# SL_FPGA_Auto_2E.net
KiCad netlist of a schematic drawn in Altium Designer
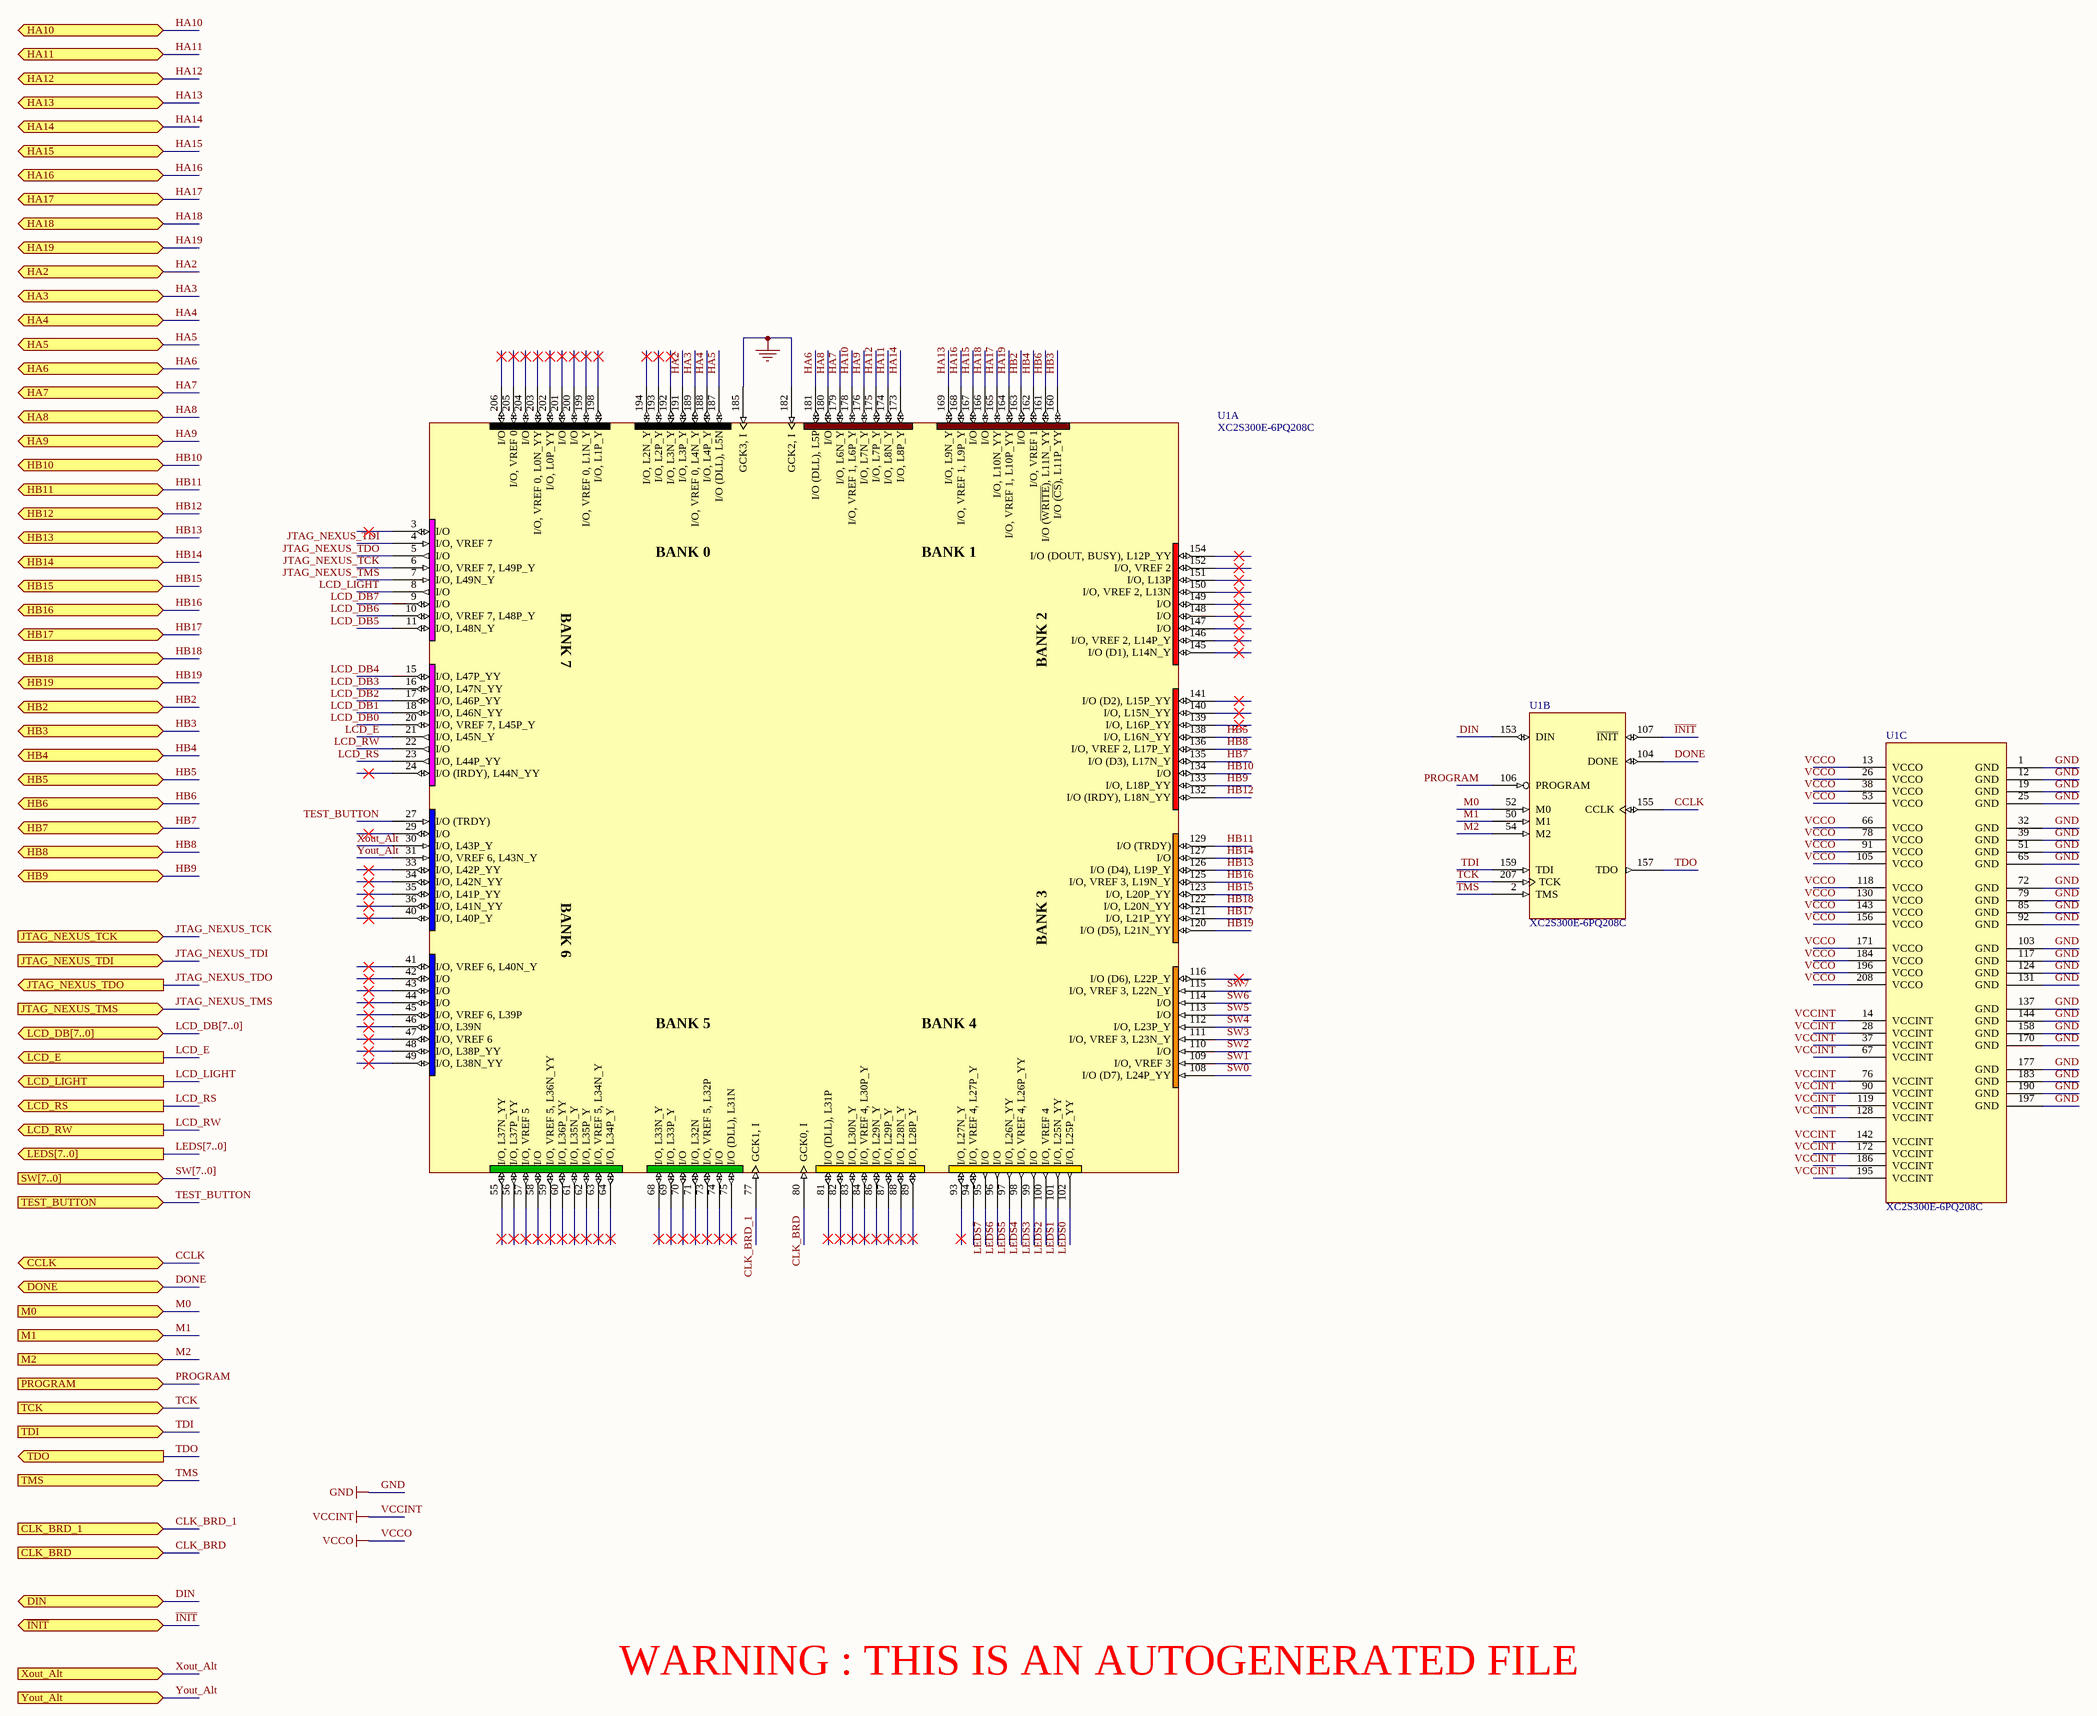
[diagram p0: SL_FPGA_Auto_2E.SchDoc]

(export (version "E")
  (design (tool "Eeschema 10.0.6"))
  (components
    (comp (ref "U1")
      (value "XC2S300E-6PQ208C")
      (footprint "Spirit_Level_Project:PQ208")
      (description "Spartan-IIE 1.8V FPGA, 208-Pin PQFP, Standard Performance, Commercial Grade")
      (fields (field (name "PUBLISHER") "Altium Limited"))
      (libsource (lib "SpiritLevel_2E") (part "XC2S300E-6PQ208C"))
    )
  )
  (nets
    (net (code "1") (name "/CCLK") (class "Default")
      (node (ref "U1") (pin "155") (pinfunction "CCLK_155") (pintype "bidirectional"))
    )
    (net (code "2") (name "/CLK_BRD") (class "Default")
      (node (ref "U1") (pin "80") (pinfunction "GCK0,_I_80") (pintype "input"))
    )
    (net (code "3") (name "/CLK_BRD_1") (class "Default")
      (node (ref "U1") (pin "77") (pinfunction "GCK1,_I_77") (pintype "input"))
    )
    (net (code "4") (name "/DIN") (class "Default")
      (node (ref "U1") (pin "153") (pinfunction "DIN_153") (pintype "bidirectional"))
    )
    (net (code "5") (name "/DONE") (class "Default")
      (node (ref "U1") (pin "104") (pinfunction "DONE_104") (pintype "bidirectional"))
    )
    (net (code "6") (name "/HA2") (class "Default")
      (node (ref "U1") (pin "191") (pinfunction "I/O,_L3P_Y_191") (pintype "bidirectional"))
    )
    (net (code "7") (name "/HA3") (class "Default")
      (node (ref "U1") (pin "189") (pinfunction "I/O,_VREF_0,_L4N_Y_189") (pintype "bidirectional"))
    )
    (net (code "8") (name "/HA4") (class "Default")
      (node (ref "U1") (pin "188") (pinfunction "I/O,_L4P_Y_188") (pintype "bidirectional"))
    )
    (net (code "9") (name "/HA5") (class "Default")
      (node (ref "U1") (pin "187") (pinfunction "I/O_(DLL),_L5N_187") (pintype "bidirectional"))
    )
    (net (code "10") (name "/HA6") (class "Default")
      (node (ref "U1") (pin "181") (pinfunction "I/O_(DLL),_L5P_181") (pintype "bidirectional"))
    )
    (net (code "11") (name "/HA7") (class "Default")
      (node (ref "U1") (pin "179") (pinfunction "I/O,_L6N_Y_179") (pintype "bidirectional"))
    )
    (net (code "12") (name "/HA8") (class "Default")
      (node (ref "U1") (pin "180") (pinfunction "I/O_180") (pintype "bidirectional"))
    )
    (net (code "13") (name "/HA9") (class "Default")
      (node (ref "U1") (pin "176") (pinfunction "I/O,_L7N_Y_176") (pintype "bidirectional"))
    )
    (net (code "14") (name "/HA10") (class "Default")
      (node (ref "U1") (pin "178") (pinfunction "I/O,_VREF_1,_L6P_Y_178") (pintype "bidirectional"))
    )
    (net (code "15") (name "/HA11") (class "Default")
      (node (ref "U1") (pin "174") (pinfunction "I/O,_L8N_Y_174") (pintype "bidirectional"))
    )
    (net (code "16") (name "/HA12") (class "Default")
      (node (ref "U1") (pin "175") (pinfunction "I/O,_L7P_Y_175") (pintype "bidirectional"))
    )
    (net (code "17") (name "/HA13") (class "Default")
      (node (ref "U1") (pin "169") (pinfunction "I/O,_L9N_Y_169") (pintype "bidirectional"))
    )
    (net (code "18") (name "/HA14") (class "Default")
      (node (ref "U1") (pin "173") (pinfunction "I/O,_L8P_Y_173") (pintype "bidirectional"))
    )
    (net (code "19") (name "/HA15") (class "Default")
      (node (ref "U1") (pin "167") (pinfunction "I/O_167") (pintype "bidirectional"))
    )
    (net (code "20") (name "/HA16") (class "Default")
      (node (ref "U1") (pin "168") (pinfunction "I/O,_VREF_1,_L9P_Y_168") (pintype "bidirectional"))
    )
    (net (code "21") (name "/HA17") (class "Default")
      (node (ref "U1") (pin "165") (pinfunction "I/O,_L10N_YY_165") (pintype "bidirectional"))
    )
    (net (code "22") (name "/HA18") (class "Default")
      (node (ref "U1") (pin "166") (pinfunction "I/O_166") (pintype "bidirectional"))
    )
    (net (code "23") (name "/HA19") (class "Default")
      (node (ref "U1") (pin "164") (pinfunction "I/O,_VREF_1,_L10P_YY_164") (pintype "bidirectional"))
    )
    (net (code "24") (name "/HB2") (class "Default")
      (node (ref "U1") (pin "163") (pinfunction "I/O_163") (pintype "bidirectional"))
    )
    (net (code "25") (name "/HB3") (class "Default")
      (node (ref "U1") (pin "160") (pinfunction "I/O_(~{CS}),_L11P_YY_160") (pintype "bidirectional"))
    )
    (net (code "26") (name "/HB4") (class "Default")
      (node (ref "U1") (pin "162") (pinfunction "I/O,_VREF_1_162") (pintype "bidirectional"))
    )
    (net (code "27") (name "/HB5") (class "Default")
      (node (ref "U1") (pin "138") (pinfunction "I/O,_L16N_YY_138") (pintype "bidirectional"))
    )
    (net (code "28") (name "/HB6") (class "Default")
      (node (ref "U1") (pin "161") (pinfunction "I/O_(~{WRITE}),_L11N_YY_161") (pintype "bidirectional"))
    )
    (net (code "29") (name "/HB7") (class "Default")
      (node (ref "U1") (pin "135") (pinfunction "I/O_(D3),_L17N_Y_135") (pintype "bidirectional"))
    )
    (net (code "30") (name "/HB8") (class "Default")
      (node (ref "U1") (pin "136") (pinfunction "I/O,_VREF_2,_L17P_Y_136") (pintype "bidirectional"))
    )
    (net (code "31") (name "/HB9") (class "Default")
      (node (ref "U1") (pin "133") (pinfunction "I/O,_L18P_YY_133") (pintype "bidirectional"))
    )
    (net (code "32") (name "/HB10") (class "Default")
      (node (ref "U1") (pin "134") (pinfunction "I/O_134") (pintype "bidirectional"))
    )
    (net (code "33") (name "/HB11") (class "Default")
      (node (ref "U1") (pin "129") (pinfunction "I/O_(TRDY)_129") (pintype "bidirectional"))
    )
    (net (code "34") (name "/HB12") (class "Default")
      (node (ref "U1") (pin "132") (pinfunction "I/O_(IRDY),_L18N_YY_132") (pintype "bidirectional"))
    )
    (net (code "35") (name "/HB13") (class "Default")
      (node (ref "U1") (pin "126") (pinfunction "I/O_(D4),_L19P_Y_126") (pintype "bidirectional"))
    )
    (net (code "36") (name "/HB14") (class "Default")
      (node (ref "U1") (pin "127") (pinfunction "I/O_127") (pintype "bidirectional"))
    )
    (net (code "37") (name "/HB15") (class "Default")
      (node (ref "U1") (pin "123") (pinfunction "I/O,_L20P_YY_123") (pintype "bidirectional"))
    )
    (net (code "38") (name "/HB16") (class "Default")
      (node (ref "U1") (pin "125") (pinfunction "I/O,_VREF_3,_L19N_Y_125") (pintype "bidirectional"))
    )
    (net (code "39") (name "/HB17") (class "Default")
      (node (ref "U1") (pin "121") (pinfunction "I/O,_L21P_YY_121") (pintype "bidirectional"))
    )
    (net (code "40") (name "/HB18") (class "Default")
      (node (ref "U1") (pin "122") (pinfunction "I/O,_L20N_YY_122") (pintype "bidirectional"))
    )
    (net (code "41") (name "/HB19") (class "Default")
      (node (ref "U1") (pin "120") (pinfunction "I/O_(D5),_L21N_YY_120") (pintype "bidirectional"))
    )
    (net (code "42") (name "/JTAG_NEXUS_TCK") (class "Default")
      (node (ref "U1") (pin "6") (pinfunction "I/O,_VREF_7,_L49P_Y_6") (pintype "input"))
    )
    (net (code "43") (name "/JTAG_NEXUS_TDI") (class "Default")
      (node (ref "U1") (pin "4") (pinfunction "I/O,_VREF_7_4") (pintype "input"))
    )
    (net (code "44") (name "/JTAG_NEXUS_TDO") (class "Default")
      (node (ref "U1") (pin "5") (pinfunction "I/O_5") (pintype "output"))
    )
    (net (code "45") (name "/JTAG_NEXUS_TMS") (class "Default")
      (node (ref "U1") (pin "7") (pinfunction "I/O,_L49N_Y_7") (pintype "input"))
    )
    (net (code "46") (name "/LCD_DB0") (class "Default")
      (node (ref "U1") (pin "20") (pinfunction "I/O,_VREF_7,_L45P_Y_20") (pintype "bidirectional"))
    )
    (net (code "47") (name "/LCD_DB1") (class "Default")
      (node (ref "U1") (pin "18") (pinfunction "I/O,_L46N_YY_18") (pintype "bidirectional"))
    )
    (net (code "48") (name "/LCD_DB2") (class "Default")
      (node (ref "U1") (pin "17") (pinfunction "I/O,_L46P_YY_17") (pintype "bidirectional"))
    )
    (net (code "49") (name "/LCD_DB3") (class "Default")
      (node (ref "U1") (pin "16") (pinfunction "I/O,_L47N_YY_16") (pintype "bidirectional"))
    )
    (net (code "50") (name "/LCD_DB4") (class "Default")
      (node (ref "U1") (pin "15") (pinfunction "I/O,_L47P_YY_15") (pintype "bidirectional"))
    )
    (net (code "51") (name "/LCD_DB5") (class "Default")
      (node (ref "U1") (pin "11") (pinfunction "I/O,_L48N_Y_11") (pintype "bidirectional"))
    )
    (net (code "52") (name "/LCD_DB6") (class "Default")
      (node (ref "U1") (pin "10") (pinfunction "I/O,_VREF_7,_L48P_Y_10") (pintype "bidirectional"))
    )
    (net (code "53") (name "/LCD_DB7") (class "Default")
      (node (ref "U1") (pin "9") (pinfunction "I/O_9") (pintype "bidirectional"))
    )
    (net (code "55") (name "/LCD_E") (class "Default")
      (node (ref "U1") (pin "21") (pinfunction "I/O,_L45N_Y_21") (pintype "output"))
    )
    (net (code "56") (name "/LCD_LIGHT") (class "Default")
      (node (ref "U1") (pin "8") (pinfunction "I/O_8") (pintype "output"))
    )
    (net (code "57") (name "/LCD_RS") (class "Default")
      (node (ref "U1") (pin "23") (pinfunction "I/O,_L44P_YY_23") (pintype "output"))
    )
    (net (code "58") (name "/LCD_RW") (class "Default")
      (node (ref "U1") (pin "22") (pinfunction "I/O_22") (pintype "output"))
    )
    (net (code "59") (name "/LEDS0") (class "Default")
      (node (ref "U1") (pin "102") (pinfunction "I/O,_L25P_YY_102") (pintype "output"))
    )
    (net (code "60") (name "/LEDS1") (class "Default")
      (node (ref "U1") (pin "101") (pinfunction "I/O,_L25N_YY_101") (pintype "output"))
    )
    (net (code "61") (name "/LEDS2") (class "Default")
      (node (ref "U1") (pin "100") (pinfunction "I/O,_VREF_4_100") (pintype "output"))
    )
    (net (code "62") (name "/LEDS3") (class "Default")
      (node (ref "U1") (pin "99") (pinfunction "I/O_99") (pintype "output"))
    )
    (net (code "63") (name "/LEDS4") (class "Default")
      (node (ref "U1") (pin "98") (pinfunction "I/O,_VREF_4,_L26P_YY_98") (pintype "output"))
    )
    (net (code "64") (name "/LEDS5") (class "Default")
      (node (ref "U1") (pin "97") (pinfunction "I/O,_L26N_YY_97") (pintype "output"))
    )
    (net (code "65") (name "/LEDS6") (class "Default")
      (node (ref "U1") (pin "96") (pinfunction "I/O_96") (pintype "output"))
    )
    (net (code "66") (name "/LEDS7") (class "Default")
      (node (ref "U1") (pin "95") (pinfunction "I/O_95") (pintype "output"))
    )
    (net (code "68") (name "/M0") (class "Default")
      (node (ref "U1") (pin "52") (pinfunction "M0_52") (pintype "input"))
    )
    (net (code "69") (name "/M1") (class "Default")
      (node (ref "U1") (pin "50") (pinfunction "M1_50") (pintype "input"))
    )
    (net (code "70") (name "/M2") (class "Default")
      (node (ref "U1") (pin "54") (pinfunction "M2_54") (pintype "input"))
    )
    (net (code "71") (name "/PROGRAM") (class "Default")
      (node (ref "U1") (pin "106") (pinfunction "PROGRAM_106") (pintype "input"))
    )
    (net (code "72") (name "/SW0") (class "Default")
      (node (ref "U1") (pin "108") (pinfunction "I/O_(D7),_L24P_YY_108") (pintype "input"))
    )
    (net (code "73") (name "/SW1") (class "Default")
      (node (ref "U1") (pin "109") (pinfunction "I/O,_VREF_3_109") (pintype "input"))
    )
    (net (code "74") (name "/SW2") (class "Default")
      (node (ref "U1") (pin "110") (pinfunction "I/O_110") (pintype "input"))
    )
    (net (code "75") (name "/SW3") (class "Default")
      (node (ref "U1") (pin "111") (pinfunction "I/O,_VREF_3,_L23N_Y_111") (pintype "input"))
    )
    (net (code "76") (name "/SW4") (class "Default")
      (node (ref "U1") (pin "112") (pinfunction "I/O,_L23P_Y_112") (pintype "input"))
    )
    (net (code "77") (name "/SW5") (class "Default")
      (node (ref "U1") (pin "113") (pinfunction "I/O_113") (pintype "input"))
    )
    (net (code "78") (name "/SW6") (class "Default")
      (node (ref "U1") (pin "114") (pinfunction "I/O_114") (pintype "input"))
    )
    (net (code "79") (name "/SW7") (class "Default")
      (node (ref "U1") (pin "115") (pinfunction "I/O,_VREF_3,_L22N_Y_115") (pintype "input"))
    )
    (net (code "81") (name "/TCK") (class "Default")
      (node (ref "U1") (pin "207") (pinfunction "TCK_207") (pintype "input"))
    )
    (net (code "82") (name "/TDI") (class "Default")
      (node (ref "U1") (pin "159") (pinfunction "TDI_159") (pintype "input"))
    )
    (net (code "83") (name "/TDO") (class "Default")
      (node (ref "U1") (pin "157") (pinfunction "TDO_157") (pintype "output"))
    )
    (net (code "84") (name "/TEST_BUTTON") (class "Default")
      (node (ref "U1") (pin "27") (pinfunction "I/O_(TRDY)_27") (pintype "input"))
    )
    (net (code "85") (name "/TMS") (class "Default")
      (node (ref "U1") (pin "2") (pinfunction "TMS_2") (pintype "input"))
    )
    (net (code "86") (name "/Xout_Alt") (class "Default")
      (node (ref "U1") (pin "30") (pinfunction "I/O,_L43P_Y_30") (pintype "input"))
    )
    (net (code "87") (name "/Yout_Alt") (class "Default")
      (node (ref "U1") (pin "31") (pinfunction "I/O,_VREF_6,_L43N_Y_31") (pintype "input"))
    )
    (net (code "88") (name "/~{INIT}") (class "Default")
      (node (ref "U1") (pin "107") (pinfunction "~{INIT}_107") (pintype "bidirectional"))
    )
    (net (code "89") (name "GND") (class "Default")
      (node (ref "U1") (pin "1") (pinfunction "GND_1") (pintype "power_in"))
      (node (ref "U1") (pin "103") (pinfunction "GND_103") (pintype "power_in"))
      (node (ref "U1") (pin "117") (pinfunction "GND_117") (pintype "power_in"))
      (node (ref "U1") (pin "12") (pinfunction "GND_12") (pintype "power_in"))
      (node (ref "U1") (pin "124") (pinfunction "GND_124") (pintype "power_in"))
      (node (ref "U1") (pin "131") (pinfunction "GND_131") (pintype "power_in"))
      (node (ref "U1") (pin "137") (pinfunction "GND_137") (pintype "power_in"))
      (node (ref "U1") (pin "144") (pinfunction "GND_144") (pintype "power_in"))
      (node (ref "U1") (pin "158") (pinfunction "GND_158") (pintype "power_in"))
      (node (ref "U1") (pin "170") (pinfunction "GND_170") (pintype "power_in"))
      (node (ref "U1") (pin "177") (pinfunction "GND_177") (pintype "power_in"))
      (node (ref "U1") (pin "182") (pinfunction "GCK2,_I_182") (pintype "input"))
      (node (ref "U1") (pin "183") (pinfunction "GND_183") (pintype "power_in"))
      (node (ref "U1") (pin "185") (pinfunction "GCK3,_I_185") (pintype "input"))
      (node (ref "U1") (pin "19") (pinfunction "GND_19") (pintype "power_in"))
      (node (ref "U1") (pin "190") (pinfunction "GND_190") (pintype "power_in"))
      (node (ref "U1") (pin "197") (pinfunction "GND_197") (pintype "power_in"))
      (node (ref "U1") (pin "25") (pinfunction "GND_25") (pintype "power_in"))
      (node (ref "U1") (pin "32") (pinfunction "GND_32") (pintype "power_in"))
      (node (ref "U1") (pin "39") (pinfunction "GND_39") (pintype "power_in"))
      (node (ref "U1") (pin "51") (pinfunction "GND_51") (pintype "power_in"))
      (node (ref "U1") (pin "65") (pinfunction "GND_65") (pintype "power_in"))
      (node (ref "U1") (pin "72") (pinfunction "GND_72") (pintype "power_in"))
      (node (ref "U1") (pin "79") (pinfunction "GND_79") (pintype "power_in"))
      (node (ref "U1") (pin "85") (pinfunction "GND_85") (pintype "power_in"))
      (node (ref "U1") (pin "92") (pinfunction "GND_92") (pintype "power_in"))
    )
    (net (code "90") (name "VCCINT") (class "Default")
      (node (ref "U1") (pin "119") (pinfunction "VCCINT_119") (pintype "power_in"))
      (node (ref "U1") (pin "128") (pinfunction "VCCINT_128") (pintype "power_in"))
      (node (ref "U1") (pin "14") (pinfunction "VCCINT_14") (pintype "power_in"))
      (node (ref "U1") (pin "142") (pinfunction "VCCINT_142") (pintype "power_in"))
      (node (ref "U1") (pin "172") (pinfunction "VCCINT_172") (pintype "power_in"))
      (node (ref "U1") (pin "186") (pinfunction "VCCINT_186") (pintype "power_in"))
      (node (ref "U1") (pin "195") (pinfunction "VCCINT_195") (pintype "power_in"))
      (node (ref "U1") (pin "28") (pinfunction "VCCINT_28") (pintype "power_in"))
      (node (ref "U1") (pin "37") (pinfunction "VCCINT_37") (pintype "power_in"))
      (node (ref "U1") (pin "67") (pinfunction "VCCINT_67") (pintype "power_in"))
      (node (ref "U1") (pin "76") (pinfunction "VCCINT_76") (pintype "power_in"))
      (node (ref "U1") (pin "90") (pinfunction "VCCINT_90") (pintype "power_in"))
    )
    (net (code "91") (name "VCCO") (class "Default")
      (node (ref "U1") (pin "105") (pinfunction "VCCO_105") (pintype "power_in"))
      (node (ref "U1") (pin "118") (pinfunction "VCCO_118") (pintype "power_in"))
      (node (ref "U1") (pin "13") (pinfunction "VCCO_13") (pintype "power_in"))
      (node (ref "U1") (pin "130") (pinfunction "VCCO_130") (pintype "power_in"))
      (node (ref "U1") (pin "143") (pinfunction "VCCO_143") (pintype "power_in"))
      (node (ref "U1") (pin "156") (pinfunction "VCCO_156") (pintype "power_in"))
      (node (ref "U1") (pin "171") (pinfunction "VCCO_171") (pintype "power_in"))
      (node (ref "U1") (pin "184") (pinfunction "VCCO_184") (pintype "power_in"))
      (node (ref "U1") (pin "196") (pinfunction "VCCO_196") (pintype "power_in"))
      (node (ref "U1") (pin "208") (pinfunction "VCCO_208") (pintype "power_in"))
      (node (ref "U1") (pin "26") (pinfunction "VCCO_26") (pintype "power_in"))
      (node (ref "U1") (pin "38") (pinfunction "VCCO_38") (pintype "power_in"))
      (node (ref "U1") (pin "53") (pinfunction "VCCO_53") (pintype "power_in"))
      (node (ref "U1") (pin "66") (pinfunction "VCCO_66") (pintype "power_in"))
      (node (ref "U1") (pin "78") (pinfunction "VCCO_78") (pintype "power_in"))
      (node (ref "U1") (pin "91") (pinfunction "VCCO_91") (pintype "power_in"))
    )
    (net (code "92") (name "unconnected-(U1A-I{slash}O,_L0P_YY-Pad202)") (class "Default")
      (node (ref "U1") (pin "202") (pinfunction "I/O,_L0P_YY_202") (pintype "bidirectional"))
    )
    (net (code "93") (name "unconnected-(U1A-I{slash}O,_L1P_Y-Pad198)") (class "Default")
      (node (ref "U1") (pin "198") (pinfunction "I/O,_L1P_Y_198") (pintype "bidirectional"))
    )
    (net (code "94") (name "unconnected-(U1A-I{slash}O,_L2N_Y-Pad194)") (class "Default")
      (node (ref "U1") (pin "194") (pinfunction "I/O,_L2N_Y_194") (pintype "bidirectional"))
    )
    (net (code "95") (name "unconnected-(U1A-I{slash}O,_L2P_Y-Pad193)") (class "Default")
      (node (ref "U1") (pin "193") (pinfunction "I/O,_L2P_Y_193") (pintype "bidirectional"))
    )
    (net (code "96") (name "unconnected-(U1A-I{slash}O,_L3N_Y-Pad192)") (class "Default")
      (node (ref "U1") (pin "192") (pinfunction "I/O,_L3N_Y_192") (pintype "bidirectional"))
    )
    (net (code "97") (name "unconnected-(U1A-I{slash}O,_L13P-Pad151)") (class "Default")
      (node (ref "U1") (pin "151") (pinfunction "I/O,_L13P_151") (pintype "bidirectional"))
    )
    (net (code "98") (name "unconnected-(U1A-I{slash}O,_L15N_YY-Pad140)") (class "Default")
      (node (ref "U1") (pin "140") (pinfunction "I/O,_L15N_YY_140") (pintype "bidirectional"))
    )
    (net (code "99") (name "unconnected-(U1A-I{slash}O,_L16P_YY-Pad139)") (class "Default")
      (node (ref "U1") (pin "139") (pinfunction "I/O,_L16P_YY_139") (pintype "bidirectional"))
    )
    (net (code "100") (name "unconnected-(U1A-I{slash}O,_L27N_Y-Pad93)") (class "Default")
      (node (ref "U1") (pin "93") (pinfunction "I/O,_L27N_Y_93") (pintype "bidirectional"))
    )
    (net (code "101") (name "unconnected-(U1A-I{slash}O,_L28N_Y-Pad88)") (class "Default")
      (node (ref "U1") (pin "88") (pinfunction "I/O,_L28N_Y_88") (pintype "bidirectional"))
    )
    (net (code "102") (name "unconnected-(U1A-I{slash}O,_L28P_Y-Pad89)") (class "Default")
      (node (ref "U1") (pin "89") (pinfunction "I/O,_L28P_Y_89") (pintype "bidirectional"))
    )
    (net (code "103") (name "unconnected-(U1A-I{slash}O,_L29N_Y-Pad86)") (class "Default")
      (node (ref "U1") (pin "86") (pinfunction "I/O,_L29N_Y_86") (pintype "bidirectional"))
    )
    (net (code "104") (name "unconnected-(U1A-I{slash}O,_L29P_Y-Pad87)") (class "Default")
      (node (ref "U1") (pin "87") (pinfunction "I/O,_L29P_Y_87") (pintype "bidirectional"))
    )
    (net (code "105") (name "unconnected-(U1A-I{slash}O,_L30N_Y-Pad83)") (class "Default")
      (node (ref "U1") (pin "83") (pinfunction "I/O,_L30N_Y_83") (pintype "bidirectional"))
    )
    (net (code "106") (name "unconnected-(U1A-I{slash}O,_L32N-Pad71)") (class "Default")
      (node (ref "U1") (pin "71") (pinfunction "I/O,_L32N_71") (pintype "bidirectional"))
    )
    (net (code "107") (name "unconnected-(U1A-I{slash}O,_L33N_Y-Pad68)") (class "Default")
      (node (ref "U1") (pin "68") (pinfunction "I/O,_L33N_Y_68") (pintype "bidirectional"))
    )
    (net (code "108") (name "unconnected-(U1A-I{slash}O,_L33P_Y-Pad69)") (class "Default")
      (node (ref "U1") (pin "69") (pinfunction "I/O,_L33P_Y_69") (pintype "bidirectional"))
    )
    (net (code "109") (name "unconnected-(U1A-I{slash}O,_L34P_Y-Pad64)") (class "Default")
      (node (ref "U1") (pin "64") (pinfunction "I/O,_L34P_Y_64") (pintype "bidirectional"))
    )
    (net (code "110") (name "unconnected-(U1A-I{slash}O,_L35N_Y-Pad61)") (class "Default")
      (node (ref "U1") (pin "61") (pinfunction "I/O,_L35N_Y_61") (pintype "bidirectional"))
    )
    (net (code "111") (name "unconnected-(U1A-I{slash}O,_L35P_Y-Pad62)") (class "Default")
      (node (ref "U1") (pin "62") (pinfunction "I/O,_L35P_Y_62") (pintype "bidirectional"))
    )
    (net (code "112") (name "unconnected-(U1A-I{slash}O,_L36P_YY-Pad60)") (class "Default")
      (node (ref "U1") (pin "60") (pinfunction "I/O,_L36P_YY_60") (pintype "bidirectional"))
    )
    (net (code "113") (name "unconnected-(U1A-I{slash}O,_L37N_YY-Pad55)") (class "Default")
      (node (ref "U1") (pin "55") (pinfunction "I/O,_L37N_YY_55") (pintype "bidirectional"))
    )
    (net (code "114") (name "unconnected-(U1A-I{slash}O,_L37P_YY-Pad56)") (class "Default")
      (node (ref "U1") (pin "56") (pinfunction "I/O,_L37P_YY_56") (pintype "bidirectional"))
    )
    (net (code "115") (name "unconnected-(U1A-I{slash}O,_L38N_YY-Pad49)") (class "Default")
      (node (ref "U1") (pin "49") (pinfunction "I/O,_L38N_YY_49") (pintype "bidirectional"))
    )
    (net (code "116") (name "unconnected-(U1A-I{slash}O,_L38P_YY-Pad48)") (class "Default")
      (node (ref "U1") (pin "48") (pinfunction "I/O,_L38P_YY_48") (pintype "bidirectional"))
    )
    (net (code "117") (name "unconnected-(U1A-I{slash}O,_L39N-Pad46)") (class "Default")
      (node (ref "U1") (pin "46") (pinfunction "I/O,_L39N_46") (pintype "bidirectional"))
    )
    (net (code "118") (name "unconnected-(U1A-I{slash}O,_L40P_Y-Pad40)") (class "Default")
      (node (ref "U1") (pin "40") (pinfunction "I/O,_L40P_Y_40") (pintype "bidirectional"))
    )
    (net (code "119") (name "unconnected-(U1A-I{slash}O,_L41N_YY-Pad36)") (class "Default")
      (node (ref "U1") (pin "36") (pinfunction "I/O,_L41N_YY_36") (pintype "bidirectional"))
    )
    (net (code "120") (name "unconnected-(U1A-I{slash}O,_L41P_YY-Pad35)") (class "Default")
      (node (ref "U1") (pin "35") (pinfunction "I/O,_L41P_YY_35") (pintype "bidirectional"))
    )
    (net (code "121") (name "unconnected-(U1A-I{slash}O,_L42N_YY-Pad34)") (class "Default")
      (node (ref "U1") (pin "34") (pinfunction "I/O,_L42N_YY_34") (pintype "bidirectional"))
    )
    (net (code "122") (name "unconnected-(U1A-I{slash}O,_L42P_YY-Pad33)") (class "Default")
      (node (ref "U1") (pin "33") (pinfunction "I/O,_L42P_YY_33") (pintype "bidirectional"))
    )
    (net (code "123") (name "unconnected-(U1A-I{slash}O,_VREF_0,_L0N_YY-Pad203)") (class "Default")
      (node (ref "U1") (pin "203") (pinfunction "I/O,_VREF_0,_L0N_YY_203") (pintype "bidirectional"))
    )
    (net (code "124") (name "unconnected-(U1A-I{slash}O,_VREF_0,_L1N_Y-Pad199)") (class "Default")
      (node (ref "U1") (pin "199") (pinfunction "I/O,_VREF_0,_L1N_Y_199") (pintype "bidirectional"))
    )
    (net (code "125") (name "unconnected-(U1A-I{slash}O,_VREF_0-Pad205)") (class "Default")
      (node (ref "U1") (pin "205") (pinfunction "I/O,_VREF_0_205") (pintype "bidirectional"))
    )
    (net (code "126") (name "unconnected-(U1A-I{slash}O,_VREF_2,_L13N-Pad150)") (class "Default")
      (node (ref "U1") (pin "150") (pinfunction "I/O,_VREF_2,_L13N_150") (pintype "bidirectional"))
    )
    (net (code "127") (name "unconnected-(U1A-I{slash}O,_VREF_2,_L14P_Y-Pad146)") (class "Default")
      (node (ref "U1") (pin "146") (pinfunction "I/O,_VREF_2,_L14P_Y_146") (pintype "bidirectional"))
    )
    (net (code "128") (name "unconnected-(U1A-I{slash}O,_VREF_2-Pad152)") (class "Default")
      (node (ref "U1") (pin "152") (pinfunction "I/O,_VREF_2_152") (pintype "bidirectional"))
    )
    (net (code "129") (name "unconnected-(U1A-I{slash}O,_VREF_4,_L27P_Y-Pad94)") (class "Default")
      (node (ref "U1") (pin "94") (pinfunction "I/O,_VREF_4,_L27P_Y_94") (pintype "bidirectional"))
    )
    (net (code "130") (name "unconnected-(U1A-I{slash}O,_VREF_4,_L30P_Y-Pad84)") (class "Default")
      (node (ref "U1") (pin "84") (pinfunction "I/O,_VREF_4,_L30P_Y_84") (pintype "bidirectional"))
    )
    (net (code "131") (name "unconnected-(U1A-I{slash}O,_VREF_5,_L32P-Pad73)") (class "Default")
      (node (ref "U1") (pin "73") (pinfunction "I/O,_VREF_5,_L32P_73") (pintype "bidirectional"))
    )
    (net (code "132") (name "unconnected-(U1A-I{slash}O,_VREF_5,_L34N_Y-Pad63)") (class "Default")
      (node (ref "U1") (pin "63") (pinfunction "I/O,_VREF_5,_L34N_Y_63") (pintype "bidirectional"))
    )
    (net (code "133") (name "unconnected-(U1A-I{slash}O,_VREF_5,_L36N_YY-Pad59)") (class "Default")
      (node (ref "U1") (pin "59") (pinfunction "I/O,_VREF_5,_L36N_YY_59") (pintype "bidirectional"))
    )
    (net (code "134") (name "unconnected-(U1A-I{slash}O,_VREF_5-Pad57)") (class "Default")
      (node (ref "U1") (pin "57") (pinfunction "I/O,_VREF_5_57") (pintype "bidirectional"))
    )
    (net (code "135") (name "unconnected-(U1A-I{slash}O,_VREF_6,_L39P-Pad45)") (class "Default")
      (node (ref "U1") (pin "45") (pinfunction "I/O,_VREF_6,_L39P_45") (pintype "bidirectional"))
    )
    (net (code "136") (name "unconnected-(U1A-I{slash}O,_VREF_6,_L40N_Y-Pad41)") (class "Default")
      (node (ref "U1") (pin "41") (pinfunction "I/O,_VREF_6,_L40N_Y_41") (pintype "bidirectional"))
    )
    (net (code "137") (name "unconnected-(U1A-I{slash}O,_VREF_6-Pad47)") (class "Default")
      (node (ref "U1") (pin "47") (pinfunction "I/O,_VREF_6_47") (pintype "bidirectional"))
    )
    (net (code "138") (name "unconnected-(U1A-I{slash}O-Pad3)") (class "Default")
      (node (ref "U1") (pin "3") (pinfunction "I/O_3") (pintype "bidirectional"))
    )
    (net (code "139") (name "unconnected-(U1A-I{slash}O-Pad29)") (class "Default")
      (node (ref "U1") (pin "29") (pinfunction "I/O_29") (pintype "bidirectional"))
    )
    (net (code "140") (name "unconnected-(U1A-I{slash}O-Pad42)") (class "Default")
      (node (ref "U1") (pin "42") (pinfunction "I/O_42") (pintype "bidirectional"))
    )
    (net (code "141") (name "unconnected-(U1A-I{slash}O-Pad43)") (class "Default")
      (node (ref "U1") (pin "43") (pinfunction "I/O_43") (pintype "bidirectional"))
    )
    (net (code "142") (name "unconnected-(U1A-I{slash}O-Pad44)") (class "Default")
      (node (ref "U1") (pin "44") (pinfunction "I/O_44") (pintype "bidirectional"))
    )
    (net (code "143") (name "unconnected-(U1A-I{slash}O-Pad58)") (class "Default")
      (node (ref "U1") (pin "58") (pinfunction "I/O_58") (pintype "bidirectional"))
    )
    (net (code "144") (name "unconnected-(U1A-I{slash}O-Pad70)") (class "Default")
      (node (ref "U1") (pin "70") (pinfunction "I/O_70") (pintype "bidirectional"))
    )
    (net (code "145") (name "unconnected-(U1A-I{slash}O-Pad74)") (class "Default")
      (node (ref "U1") (pin "74") (pinfunction "I/O_74") (pintype "bidirectional"))
    )
    (net (code "146") (name "unconnected-(U1A-I{slash}O-Pad82)") (class "Default")
      (node (ref "U1") (pin "82") (pinfunction "I/O_82") (pintype "bidirectional"))
    )
    (net (code "147") (name "unconnected-(U1A-I{slash}O-Pad147)") (class "Default")
      (node (ref "U1") (pin "147") (pinfunction "I/O_147") (pintype "bidirectional"))
    )
    (net (code "148") (name "unconnected-(U1A-I{slash}O-Pad148)") (class "Default")
      (node (ref "U1") (pin "148") (pinfunction "I/O_148") (pintype "bidirectional"))
    )
    (net (code "149") (name "unconnected-(U1A-I{slash}O-Pad149)") (class "Default")
      (node (ref "U1") (pin "149") (pinfunction "I/O_149") (pintype "bidirectional"))
    )
    (net (code "150") (name "unconnected-(U1A-I{slash}O-Pad200)") (class "Default")
      (node (ref "U1") (pin "200") (pinfunction "I/O_200") (pintype "bidirectional"))
    )
    (net (code "151") (name "unconnected-(U1A-I{slash}O-Pad201)") (class "Default")
      (node (ref "U1") (pin "201") (pinfunction "I/O_201") (pintype "bidirectional"))
    )
    (net (code "152") (name "unconnected-(U1A-I{slash}O-Pad204)") (class "Default")
      (node (ref "U1") (pin "204") (pinfunction "I/O_204") (pintype "bidirectional"))
    )
    (net (code "153") (name "unconnected-(U1A-I{slash}O-Pad206)") (class "Default")
      (node (ref "U1") (pin "206") (pinfunction "I/O_206") (pintype "bidirectional"))
    )
    (net (code "154") (name "unconnected-(U1A-I{slash}O_(D1),_L14N_Y-Pad145)") (class "Default")
      (node (ref "U1") (pin "145") (pinfunction "I/O_(D1),_L14N_Y_145") (pintype "bidirectional"))
    )
    (net (code "155") (name "unconnected-(U1A-I{slash}O_(D2),_L15P_YY-Pad141)") (class "Default")
      (node (ref "U1") (pin "141") (pinfunction "I/O_(D2),_L15P_YY_141") (pintype "bidirectional"))
    )
    (net (code "156") (name "unconnected-(U1A-I{slash}O_(D6),_L22P_Y-Pad116)") (class "Default")
      (node (ref "U1") (pin "116") (pinfunction "I/O_(D6),_L22P_Y_116") (pintype "bidirectional"))
    )
    (net (code "157") (name "unconnected-(U1A-I{slash}O_(DLL),_L31N-Pad75)") (class "Default")
      (node (ref "U1") (pin "75") (pinfunction "I/O_(DLL),_L31N_75") (pintype "bidirectional"))
    )
    (net (code "158") (name "unconnected-(U1A-I{slash}O_(DLL),_L31P-Pad81)") (class "Default")
      (node (ref "U1") (pin "81") (pinfunction "I/O_(DLL),_L31P_81") (pintype "bidirectional"))
    )
    (net (code "159") (name "unconnected-(U1A-I{slash}O_(DOUT,_BUSY),_L12P_YY-Pad154)") (class "Default")
      (node (ref "U1") (pin "154") (pinfunction "I/O_(DOUT,_BUSY),_L12P_YY_154") (pintype "bidirectional"))
    )
    (net (code "160") (name "unconnected-(U1A-I{slash}O_(IRDY),_L44N_YY-Pad24)") (class "Default")
      (node (ref "U1") (pin "24") (pinfunction "I/O_(IRDY),_L44N_YY_24") (pintype "bidirectional"))
    )
  )
)
